# JDY08_CC2541_Breakout.net
KiCad netlist of a schematic drawn in EAGLE
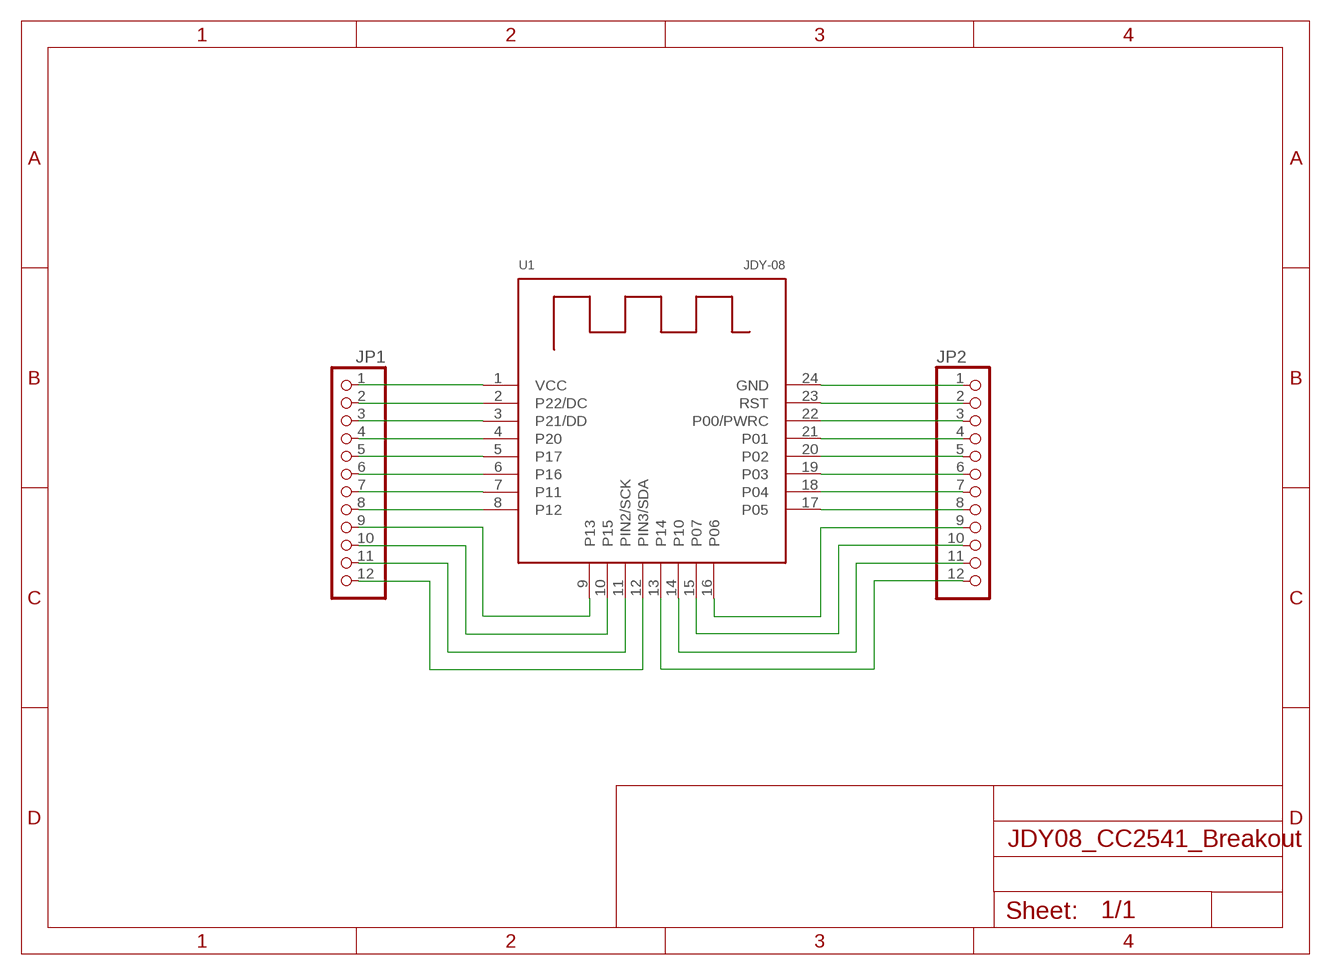
[diagram p0: schematic, sheet 1]

(export (version "E")
  (design (tool "Eeschema 10.0.6"))
  (components
    (comp (ref "JP1")
      (value "HEADER-1X1276MIL")
      (footprint "eagle-import:1X12_ROUND_76MIL")
      (libsource (lib "eagle-import") (part "HEADER-1X1276MIL"))
    )
    (comp (ref "JP2")
      (value "HEADER-1X1276MIL")
      (footprint "eagle-import:1X12_ROUND_76MIL")
      (libsource (lib "eagle-import") (part "HEADER-1X1276MIL"))
    )
    (comp (ref "U1")
      (value "JDY-08")
      (footprint "eagle-import:JDY-08")
      (libsource (lib "eagle-import") (part "JDY-08"))
    )
  )
  (nets
    (net (code "1") (name "Net-(U1-GND)") (class "Default")
      (node (ref "JP2") (pin "1") (pinfunction "1_1") (pintype "passive"))
      (node (ref "U1") (pin "24") (pinfunction "GND_24") (pintype "bidirectional"))
    )
    (net (code "2") (name "Net-(U1-P00{slash}PWRC)") (class "Default")
      (node (ref "JP2") (pin "3") (pinfunction "3_3") (pintype "passive"))
      (node (ref "U1") (pin "22") (pinfunction "P00/PWRC_22") (pintype "bidirectional"))
    )
    (net (code "3") (name "Net-(U1-P01)") (class "Default")
      (node (ref "JP2") (pin "4") (pinfunction "4_4") (pintype "passive"))
      (node (ref "U1") (pin "21") (pinfunction "P01_21") (pintype "bidirectional"))
    )
    (net (code "4") (name "Net-(U1-P02)") (class "Default")
      (node (ref "JP2") (pin "5") (pinfunction "5_5") (pintype "passive"))
      (node (ref "U1") (pin "20") (pinfunction "P02_20") (pintype "bidirectional"))
    )
    (net (code "5") (name "Net-(U1-P03)") (class "Default")
      (node (ref "JP2") (pin "6") (pinfunction "6_6") (pintype "passive"))
      (node (ref "U1") (pin "19") (pinfunction "P03_19") (pintype "bidirectional"))
    )
    (net (code "6") (name "Net-(U1-P04)") (class "Default")
      (node (ref "JP2") (pin "7") (pinfunction "7_7") (pintype "passive"))
      (node (ref "U1") (pin "18") (pinfunction "P04_18") (pintype "bidirectional"))
    )
    (net (code "7") (name "Net-(U1-P05)") (class "Default")
      (node (ref "JP2") (pin "8") (pinfunction "8_8") (pintype "passive"))
      (node (ref "U1") (pin "17") (pinfunction "P05_17") (pintype "bidirectional"))
    )
    (net (code "8") (name "Net-(U1-P06)") (class "Default")
      (node (ref "JP2") (pin "9") (pinfunction "9_9") (pintype "passive"))
      (node (ref "U1") (pin "16") (pinfunction "P06_16") (pintype "bidirectional"))
    )
    (net (code "9") (name "Net-(U1-P07)") (class "Default")
      (node (ref "JP2") (pin "10") (pinfunction "10_10") (pintype "passive"))
      (node (ref "U1") (pin "15") (pinfunction "P07_15") (pintype "bidirectional"))
    )
    (net (code "10") (name "Net-(U1-P10)") (class "Default")
      (node (ref "JP2") (pin "11") (pinfunction "11_11") (pintype "passive"))
      (node (ref "U1") (pin "14") (pinfunction "P10_14") (pintype "bidirectional"))
    )
    (net (code "11") (name "Net-(U1-P11)") (class "Default")
      (node (ref "JP1") (pin "7") (pinfunction "7_7") (pintype "passive"))
      (node (ref "U1") (pin "7") (pinfunction "P11_7") (pintype "bidirectional"))
    )
    (net (code "12") (name "Net-(U1-P12)") (class "Default")
      (node (ref "JP1") (pin "8") (pinfunction "8_8") (pintype "passive"))
      (node (ref "U1") (pin "8") (pinfunction "P12_8") (pintype "bidirectional"))
    )
    (net (code "13") (name "Net-(U1-P13)") (class "Default")
      (node (ref "JP1") (pin "9") (pinfunction "9_9") (pintype "passive"))
      (node (ref "U1") (pin "9") (pinfunction "P13_9") (pintype "bidirectional"))
    )
    (net (code "14") (name "Net-(U1-P14)") (class "Default")
      (node (ref "JP2") (pin "12") (pinfunction "12_12") (pintype "passive"))
      (node (ref "U1") (pin "13") (pinfunction "P14_13") (pintype "bidirectional"))
    )
    (net (code "15") (name "Net-(U1-P15)") (class "Default")
      (node (ref "JP1") (pin "10") (pinfunction "10_10") (pintype "passive"))
      (node (ref "U1") (pin "10") (pinfunction "P15_10") (pintype "bidirectional"))
    )
    (net (code "16") (name "Net-(U1-P16)") (class "Default")
      (node (ref "JP1") (pin "6") (pinfunction "6_6") (pintype "passive"))
      (node (ref "U1") (pin "6") (pinfunction "P16_6") (pintype "bidirectional"))
    )
    (net (code "17") (name "Net-(U1-P17)") (class "Default")
      (node (ref "JP1") (pin "5") (pinfunction "5_5") (pintype "passive"))
      (node (ref "U1") (pin "5") (pinfunction "P17_5") (pintype "bidirectional"))
    )
    (net (code "18") (name "Net-(U1-P20)") (class "Default")
      (node (ref "JP1") (pin "4") (pinfunction "4_4") (pintype "passive"))
      (node (ref "U1") (pin "4") (pinfunction "P20_4") (pintype "bidirectional"))
    )
    (net (code "19") (name "Net-(U1-P21{slash}DD)") (class "Default")
      (node (ref "JP1") (pin "3") (pinfunction "3_3") (pintype "passive"))
      (node (ref "U1") (pin "3") (pinfunction "P21/DD_3") (pintype "bidirectional"))
    )
    (net (code "20") (name "Net-(U1-P22{slash}DC)") (class "Default")
      (node (ref "JP1") (pin "2") (pinfunction "2_2") (pintype "passive"))
      (node (ref "U1") (pin "2") (pinfunction "P22/DC_2") (pintype "bidirectional"))
    )
    (net (code "21") (name "Net-(U1-PIN2{slash}SCK)") (class "Default")
      (node (ref "JP1") (pin "11") (pinfunction "11_11") (pintype "passive"))
      (node (ref "U1") (pin "11") (pinfunction "PIN2/SCK_11") (pintype "bidirectional"))
    )
    (net (code "22") (name "Net-(U1-PIN3{slash}SDA)") (class "Default")
      (node (ref "JP1") (pin "12") (pinfunction "12_12") (pintype "passive"))
      (node (ref "U1") (pin "12") (pinfunction "PIN3/SDA_12") (pintype "bidirectional"))
    )
    (net (code "23") (name "Net-(U1-RST)") (class "Default")
      (node (ref "JP2") (pin "2") (pinfunction "2_2") (pintype "passive"))
      (node (ref "U1") (pin "23") (pinfunction "RST_23") (pintype "bidirectional"))
    )
    (net (code "24") (name "Net-(U1-VCC)") (class "Default")
      (node (ref "JP1") (pin "1") (pinfunction "1_1") (pintype "passive"))
      (node (ref "U1") (pin "1") (pinfunction "VCC_1") (pintype "bidirectional"))
    )
  )
)
